# HF_Port.net
KiCad netlist of a schematic drawn in Altium Designer
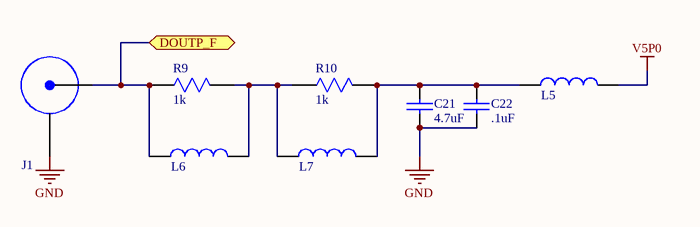
[diagram p0: HF_Port.SchDoc]

(export (version "E")
  (design (tool "Eeschema 10.0.6"))
  (components
    (comp (ref "C21")
      (value "4.7uF")
      (footprint "SMD Capacitor 0603")
      (libsource (lib "DA_Component_Library") (part "Capacitor"))
    )
    (comp (ref "C22")
      (value ".1uF")
      (footprint "SMD CAP 0402")
      (libsource (lib "DA_Component_Library") (part "Capacitor"))
    )
    (comp (ref "J1")
      (value "Coax Connector")
      (footprint "Coax Direct Solder ThroughHoles")
      (libsource (lib "DA_Component_Library") (part "Coax Connector"))
    )
    (comp (ref "L5")
      (value "Ferrite Bead")
      (footprint "BLM18KG601SN1D")
      (libsource (lib "DA_Component_Library") (part "Ferrite Bead"))
    )
    (comp (ref "L6")
      (value "Ferrite Bead")
      (footprint "CIG21L4R7MNE")
      (libsource (lib "DA_Component_Library") (part "Ferrite Bead"))
    )
    (comp (ref "L7")
      (value "Ferrite Bead")
      (footprint "CBC3225T101MR")
      (libsource (lib "DA_Component_Library") (part "Ferrite Bead"))
    )
    (comp (ref "R9")
      (value "1k")
      (footprint "SMD RES 0402")
      (libsource (lib "DA_Component_Library") (part "Resistor"))
    )
    (comp (ref "R10")
      (value "1k")
      (footprint "SMD RES 0402")
      (libsource (lib "DA_Component_Library") (part "Resistor"))
    )
  )
  (nets
    (net (code "1") (name "/DOUTP_F") (class "Default")
      (node (ref "J1") (pin "0") (pinfunction "0_0") (pintype "passive"))
      (node (ref "L6") (pin "1") (pinfunction "1_1") (pintype "passive"))
      (node (ref "R9") (pin "0") (pinfunction "0_0") (pintype "passive"))
    )
    (net (code "2") (name "GND") (class "Default")
      (node (ref "C21") (pin "1") (pinfunction "1_1") (pintype "passive"))
      (node (ref "C22") (pin "1") (pinfunction "1_1") (pintype "passive"))
      (node (ref "J1") (pin "1") (pinfunction "1_1") (pintype "passive"))
    )
    (net (code "3") (name "Net-(C21-Pad0)") (class "Default")
      (node (ref "C21") (pin "0") (pinfunction "0_0") (pintype "passive"))
      (node (ref "C22") (pin "0") (pinfunction "0_0") (pintype "passive"))
      (node (ref "L5") (pin "1") (pinfunction "1_1") (pintype "passive"))
      (node (ref "L7") (pin "2") (pinfunction "2_2") (pintype "passive"))
      (node (ref "R10") (pin "1") (pinfunction "1_1") (pintype "passive"))
    )
    (net (code "4") (name "Net-(L6-Pad2)") (class "Default")
      (node (ref "L6") (pin "2") (pinfunction "2_2") (pintype "passive"))
      (node (ref "L7") (pin "1") (pinfunction "1_1") (pintype "passive"))
      (node (ref "R10") (pin "0") (pinfunction "0_0") (pintype "passive"))
      (node (ref "R9") (pin "1") (pinfunction "1_1") (pintype "passive"))
    )
    (net (code "5") (name "V5P0") (class "Default")
      (node (ref "L5") (pin "2") (pinfunction "2_2") (pintype "passive"))
    )
  )
)
